# usb_ethernet.net
KiCad netlist of a schematic drawn in Altium Designer
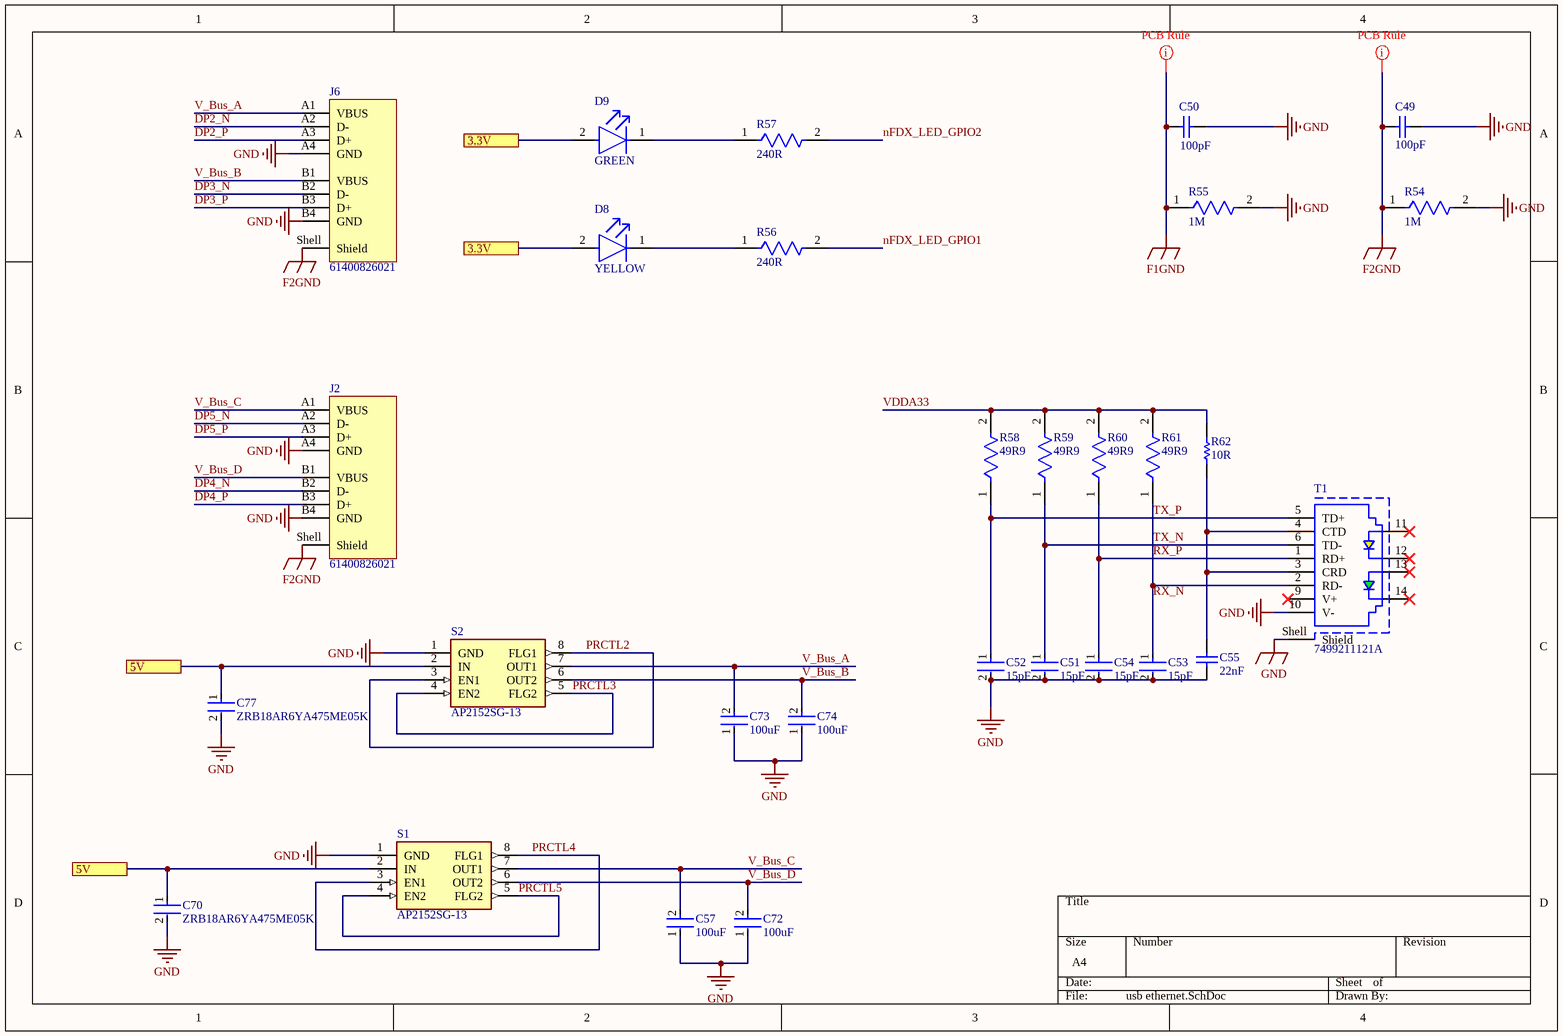
[diagram p0: usb ethernet.SchDoc]

(export (version "E")
  (design (tool "Eeschema 10.0.6"))
  (components
    (comp (ref "C49")
      (value "100pF")
      (footprint "CAPC1608X95X40LL15T15")
      (fields (field (name "PART NUMBER") "VJ0603Y101KXQPW1BC") (field (name "MANUFACTURER") "Vitramon"))
      (libsource (lib "Altium Content Vault") (part "CAP"))
    )
    (comp (ref "C50")
      (value "100pF")
      (footprint "CAPC1608X95X40LL15T15")
      (fields (field (name "PART NUMBER") "VJ0603Y101KXQPW1BC") (field (name "MANUFACTURER") "Vitramon"))
      (libsource (lib "Altium Content Vault") (part "CAP"))
    )
    (comp (ref "C51")
      (value "15pF")
      (footprint "FP-GRM21A-0_2-IPC_C")
      (description "Chip Multilayer Ceramic Capacitors for General Purpose, 0805, 15pF, C0G, 30ppm/°C, 1%, 250V")
      (libsource (lib "Altium Content Vault") (part "02cd4be3c70576c341d710602a673aa"))
    )
    (comp (ref "C52")
      (value "15pF")
      (footprint "FP-GRM21A-0_2-IPC_C")
      (description "Chip Multilayer Ceramic Capacitors for General Purpose, 0805, 15pF, C0G, 30ppm/°C, 1%, 250V")
      (libsource (lib "Altium Content Vault") (part "02cd4be3c70576c341d710602a673aa"))
    )
    (comp (ref "C53")
      (value "15pF")
      (footprint "FP-GRM21A-0_2-IPC_C")
      (description "Chip Multilayer Ceramic Capacitors for General Purpose, 0805, 15pF, C0G, 30ppm/°C, 1%, 250V")
      (libsource (lib "Altium Content Vault") (part "02cd4be3c70576c341d710602a673aa"))
    )
    (comp (ref "C54")
      (value "15pF")
      (footprint "FP-GRM21A-0_2-IPC_C")
      (description "Chip Multilayer Ceramic Capacitors for General Purpose, 0805, 15pF, C0G, 30ppm/°C, 1%, 250V")
      (libsource (lib "Altium Content Vault") (part "02cd4be3c70576c341d710602a673aa"))
    )
    (comp (ref "C55")
      (value "22nF")
      (footprint "CAPC2013X94X50ML20T25")
      (fields
        (field (name "PART NUMBER") "08055C223KAZ2A")
        (field (name "MANUFACTURER") "AVX Interconnect / Elco")
      )
      (libsource (lib "Altium Content Vault") (part "CAP"))
    )
    (comp (ref "C57")
      (value "100uF")
      (footprint "FP-GRM31C-0_3-e0_3_0_8-MFG")
      (description "Chip Multilayer Ceramic Capacitors for General Purpose, 1206, 100uF, X5R, 15%, 20%, 6.3V")
      (libsource (lib "Altium Content Vault") (part "f23184f103b6ebe33a8c269c53dcba6"))
    )
    (comp (ref "C70")
      (value "ZRB18AR6YA475ME05K")
      (footprint "FP-ZRB18A-0_2-MFG")
      (description "Chip Multilayer Ceramic Capacitors 4.7μF ±20% 35Vdc X5R ±15.0% 0603 (1608M)")
      (libsource (lib "Altium Content Vault") (part "b4654b650e69147ec39a6b967a45e02"))
    )
    (comp (ref "C72")
      (value "100uF")
      (footprint "FP-GRM31C-0_3-e0_3_0_8-MFG")
      (description "Chip Multilayer Ceramic Capacitors for General Purpose, 1206, 100uF, X5R, 15%, 20%, 6.3V")
      (libsource (lib "Altium Content Vault") (part "f23184f103b6ebe33a8c269c53dcba6"))
    )
    (comp (ref "C73")
      (value "100uF")
      (footprint "FP-GRM31C-0_3-e0_3_0_8-MFG")
      (description "Chip Multilayer Ceramic Capacitors for General Purpose, 1206, 100uF, X5R, 15%, 20%, 6.3V")
      (libsource (lib "Altium Content Vault") (part "f23184f103b6ebe33a8c269c53dcba6"))
    )
    (comp (ref "C74")
      (value "100uF")
      (footprint "FP-GRM31C-0_3-e0_3_0_8-MFG")
      (description "Chip Multilayer Ceramic Capacitors for General Purpose, 1206, 100uF, X5R, 15%, 20%, 6.3V")
      (libsource (lib "Altium Content Vault") (part "f23184f103b6ebe33a8c269c53dcba6"))
    )
    (comp (ref "C77")
      (value "ZRB18AR6YA475ME05K")
      (footprint "FP-ZRB18A-0_2-MFG")
      (description "Chip Multilayer Ceramic Capacitors 4.7μF ±20% 35Vdc X5R ±15.0% 0603 (1608M)")
      (libsource (lib "Altium Content Vault") (part "b4654b650e69147ec39a6b967a45e02"))
    )
    (comp (ref "D8")
      (value "YELLOW")
      (footprint "FP-APHCM2012SYCK-F01-MFG")
      (description "LED YELLOW CLEAR CHIP SMD")
      (libsource (lib "Altium Content Vault") (part "8706943c75ba83719d021d2fdc84c58"))
    )
    (comp (ref "D9")
      (value "GREEN")
      (footprint "FP-XZVG53W-1-MFG")
      (description "LED GREEN CLEAR CHIP SMD")
      (libsource (lib "Altium Content Vault") (part "8706943c75ba83719d021d2fdc84c58"))
    )
    (comp (ref "J2")
      (value "61400826021")
      (footprint "61400826021")
      (libsource (lib "Altium Content Vault") (part "USB 2.0_Type A_Receptacle_2 Port"))
    )
    (comp (ref "J6")
      (value "61400826021")
      (footprint "61400826021")
      (libsource (lib "Altium Content Vault") (part "USB 2.0_Type A_Receptacle_2 Port"))
    )
    (comp (ref "R54")
      (value "1M")
      (footprint "FP-RMCF0805-MFG")
      (description "1MΩ ±5% 0.125W 0805 Thick Film Chip Resistor AEC-Q200 compliant")
      (fields (field (name "TOLERANCE") "5%"))
      (libsource (lib "Altium Content Vault") (part "1029c3af85768c4190bb7ad29bc67b5"))
    )
    (comp (ref "R55")
      (value "1M")
      (footprint "FP-RMCF0805-MFG")
      (description "1MΩ ±5% 0.125W 0805 Thick Film Chip Resistor AEC-Q200 compliant")
      (fields (field (name "TOLERANCE") "5%"))
      (libsource (lib "Altium Content Vault") (part "1029c3af85768c4190bb7ad29bc67b5"))
    )
    (comp (ref "R56")
      (value "240R")
      (footprint "FP-RMCF0201-IPC_C")
      (description "240Ω ±1% 0.05W 0201 Thick Film Chip Resistor AEC-Q200 compliant")
      (fields (field (name "TOLERANCE") "1%"))
      (libsource (lib "Altium Content Vault") (part "1029c3af85768c4190bb7ad29bc67b5"))
    )
    (comp (ref "R57")
      (value "240R")
      (footprint "FP-RMCF0201-IPC_C")
      (description "240Ω ±1% 0.05W 0201 Thick Film Chip Resistor AEC-Q200 compliant")
      (fields (field (name "TOLERANCE") "1%"))
      (libsource (lib "Altium Content Vault") (part "1029c3af85768c4190bb7ad29bc67b5"))
    )
    (comp (ref "R58")
      (value "49R9")
      (footprint "FP-CPF0603-MFG")
      (description "RES SMD 49.9Ω 0.1% 1/16W 0603")
      (fields (field (name "TOLERANCE") "0.1%") (field (name "MANUFACTURER") "TE Connectivity"))
      (libsource (lib "Altium Content Vault") (part "1029c3af85768c4190bb7ad29bc67b5"))
    )
    (comp (ref "R59")
      (value "49R9")
      (footprint "FP-CPF0603-MFG")
      (description "RES SMD 49.9Ω 0.1% 1/16W 0603")
      (fields (field (name "TOLERANCE") "0.1%") (field (name "MANUFACTURER") "TE Connectivity"))
      (libsource (lib "Altium Content Vault") (part "1029c3af85768c4190bb7ad29bc67b5"))
    )
    (comp (ref "R60")
      (value "49R9")
      (footprint "FP-CPF0603-MFG")
      (description "RES SMD 49.9Ω 0.1% 1/16W 0603")
      (fields (field (name "TOLERANCE") "0.1%") (field (name "MANUFACTURER") "TE Connectivity"))
      (libsource (lib "Altium Content Vault") (part "1029c3af85768c4190bb7ad29bc67b5"))
    )
    (comp (ref "R61")
      (value "49R9")
      (footprint "FP-CPF0603-MFG")
      (description "RES SMD 49.9Ω 0.1% 1/16W 0603")
      (fields (field (name "TOLERANCE") "0.1%") (field (name "MANUFACTURER") "TE Connectivity"))
      (libsource (lib "Altium Content Vault") (part "1029c3af85768c4190bb7ad29bc67b5"))
    )
    (comp (ref "R62")
      (value "10R")
      (footprint "RESC1005X40X25LL10T10")
      (fields (field (name "PART NUMBER") "SG73P1ETTP10R0F") (field (name "MANUFACTURER") "KOA Speer"))
      (libsource (lib "Altium Content Vault") (part "RES"))
    )
    (comp (ref "S1")
      (value "AP2152SG-13")
      (footprint "SamacSys:SOIC127P600X175-8N")
      (description "Switch")
      (fields (field (name "MOUSER PART NUMBER") "621-AP2152SG-13"))
      (libsource (lib "*") (part "AP2152SG-13"))
    )
    (comp (ref "S2")
      (value "AP2152SG-13")
      (footprint "SamacSys:SOIC127P600X175-8N")
      (description "Switch")
      (fields (field (name "MOUSER PART NUMBER") "621-AP2152SG-13"))
      (libsource (lib "*") (part "AP2152SG-13"))
    )
    (comp (ref "T1")
      (value "7499211121A")
      (footprint "7499211121A")
      (description "7499211121A Modular Connectors / Ethernet Connectors WE-RJ45 Int XFMR THT 1x1")
      (libsource (lib "Altium Content Vault") (part "7499211121A"))
    )
  )
  (nets
    (net (code "1") (name "/3.3V") (class "Default")
      (node (ref "D8") (pin "2") (pinfunction "A_2") (pintype "passive"))
      (node (ref "D9") (pin "2") (pinfunction "A_2") (pintype "passive"))
    )
    (net (code "2") (name "/5V") (class "Default")
      (node (ref "C70") (pin "1") (pinfunction "1_1") (pintype "passive"))
      (node (ref "C77") (pin "1") (pinfunction "1_1") (pintype "passive"))
      (node (ref "S1") (pin "2") (pinfunction "IN_2") (pintype "power_in"))
      (node (ref "S2") (pin "2") (pinfunction "IN_2") (pintype "power_in"))
    )
    (net (code "3") (name "/DP2_N") (class "Default")
      (node (ref "J6") (pin "A2") (pinfunction "D-_A2") (pintype "passive"))
    )
    (net (code "4") (name "/DP2_P") (class "Default")
      (node (ref "J6") (pin "A3") (pinfunction "D+_A3") (pintype "passive"))
    )
    (net (code "5") (name "/DP3_N") (class "Default")
      (node (ref "J6") (pin "B2") (pinfunction "D-_B2") (pintype "passive"))
    )
    (net (code "6") (name "/DP3_P") (class "Default")
      (node (ref "J6") (pin "B3") (pinfunction "D+_B3") (pintype "passive"))
    )
    (net (code "7") (name "/DP4_N") (class "Default")
      (node (ref "J2") (pin "B2") (pinfunction "D-_B2") (pintype "passive"))
    )
    (net (code "8") (name "/DP4_P") (class "Default")
      (node (ref "J2") (pin "B3") (pinfunction "D+_B3") (pintype "passive"))
    )
    (net (code "9") (name "/DP5_N") (class "Default")
      (node (ref "J2") (pin "A2") (pinfunction "D-_A2") (pintype "passive"))
    )
    (net (code "10") (name "/DP5_P") (class "Default")
      (node (ref "J2") (pin "A3") (pinfunction "D+_A3") (pintype "passive"))
    )
    (net (code "11") (name "/PRCTL2") (class "Default")
      (node (ref "S2") (pin "3") (pinfunction "EN1_3") (pintype "input"))
      (node (ref "S2") (pin "8") (pinfunction "FLG1_8") (pintype "output"))
    )
    (net (code "12") (name "/PRCTL3") (class "Default")
      (node (ref "S2") (pin "4") (pinfunction "EN2_4") (pintype "input"))
      (node (ref "S2") (pin "5") (pinfunction "FLG2_5") (pintype "output"))
    )
    (net (code "13") (name "/PRCTL4") (class "Default")
      (node (ref "S1") (pin "3") (pinfunction "EN1_3") (pintype "input"))
      (node (ref "S1") (pin "8") (pinfunction "FLG1_8") (pintype "output"))
    )
    (net (code "14") (name "/PRCTL5") (class "Default")
      (node (ref "S1") (pin "4") (pinfunction "EN2_4") (pintype "input"))
      (node (ref "S1") (pin "5") (pinfunction "FLG2_5") (pintype "output"))
    )
    (net (code "15") (name "/RX_N") (class "Default")
      (node (ref "C51") (pin "1") (pinfunction "1_1") (pintype "passive"))
      (node (ref "C52") (pin "1") (pinfunction "1_1") (pintype "passive"))
      (node (ref "C53") (pin "1") (pinfunction "1_1") (pintype "passive"))
      (node (ref "C54") (pin "1") (pinfunction "1_1") (pintype "passive"))
      (node (ref "R58") (pin "1") (pinfunction "1_1") (pintype "passive"))
      (node (ref "R59") (pin "1") (pinfunction "1_1") (pintype "passive"))
      (node (ref "R60") (pin "1") (pinfunction "1_1") (pintype "passive"))
      (node (ref "R61") (pin "1") (pinfunction "1_1") (pintype "passive"))
      (node (ref "T1") (pin "1") (pinfunction "RD+_1") (pintype "passive"))
      (node (ref "T1") (pin "2") (pinfunction "RD-_2") (pintype "passive"))
      (node (ref "T1") (pin "5") (pinfunction "TD+_5") (pintype "passive"))
      (node (ref "T1") (pin "6") (pinfunction "TD-_6") (pintype "passive"))
    )
    (net (code "16") (name "/VDDA33") (class "Default")
      (node (ref "R58") (pin "2") (pinfunction "2_2") (pintype "passive"))
      (node (ref "R59") (pin "2") (pinfunction "2_2") (pintype "passive"))
      (node (ref "R60") (pin "2") (pinfunction "2_2") (pintype "passive"))
      (node (ref "R61") (pin "2") (pinfunction "2_2") (pintype "passive"))
      (node (ref "R62") (pin "2") (pinfunction "2_2") (pintype "passive"))
    )
    (net (code "17") (name "/V_Bus_A") (class "Default")
      (node (ref "C73") (pin "2") (pinfunction "2_2") (pintype "passive"))
      (node (ref "J6") (pin "A1") (pinfunction "VBUS_A1") (pintype "passive"))
      (node (ref "S2") (pin "7") (pinfunction "OUT1_7") (pintype "output"))
    )
    (net (code "18") (name "/V_Bus_B") (class "Default")
      (node (ref "C74") (pin "2") (pinfunction "2_2") (pintype "passive"))
      (node (ref "J6") (pin "B1") (pinfunction "VBUS_B1") (pintype "passive"))
      (node (ref "S2") (pin "6") (pinfunction "OUT2_6") (pintype "output"))
    )
    (net (code "19") (name "/V_Bus_C") (class "Default")
      (node (ref "C57") (pin "2") (pinfunction "2_2") (pintype "passive"))
      (node (ref "J2") (pin "A1") (pinfunction "VBUS_A1") (pintype "passive"))
      (node (ref "S1") (pin "7") (pinfunction "OUT1_7") (pintype "output"))
    )
    (net (code "20") (name "/V_Bus_D") (class "Default")
      (node (ref "C72") (pin "2") (pinfunction "2_2") (pintype "passive"))
      (node (ref "J2") (pin "B1") (pinfunction "VBUS_B1") (pintype "passive"))
      (node (ref "S1") (pin "6") (pinfunction "OUT2_6") (pintype "output"))
    )
    (net (code "21") (name "/nFDX_LED_GPIO1") (class "Default")
      (node (ref "R56") (pin "2") (pinfunction "2_2") (pintype "passive"))
    )
    (net (code "22") (name "/nFDX_LED_GPIO2") (class "Default")
      (node (ref "R57") (pin "2") (pinfunction "2_2") (pintype "passive"))
    )
    (net (code "23") (name "F1GND") (class "Default")
      (node (ref "C50") (pin "1") (pinfunction "1_1") (pintype "passive"))
      (node (ref "R55") (pin "1") (pinfunction "1_1") (pintype "passive"))
    )
    (net (code "24") (name "F2GND") (class "Default")
      (node (ref "C49") (pin "1") (pinfunction "1_1") (pintype "passive"))
      (node (ref "J2") (pin "Shell") (pinfunction "Shield_Shell") (pintype "passive"))
      (node (ref "J6") (pin "Shell") (pinfunction "Shield_Shell") (pintype "passive"))
      (node (ref "R54") (pin "1") (pinfunction "1_1") (pintype "passive"))
    )
    (net (code "25") (name "GND") (class "Default")
      (node (ref "C49") (pin "2") (pinfunction "2_2") (pintype "passive"))
      (node (ref "C50") (pin "2") (pinfunction "2_2") (pintype "passive"))
      (node (ref "C51") (pin "2") (pinfunction "2_2") (pintype "passive"))
      (node (ref "C52") (pin "2") (pinfunction "2_2") (pintype "passive"))
      (node (ref "C53") (pin "2") (pinfunction "2_2") (pintype "passive"))
      (node (ref "C54") (pin "2") (pinfunction "2_2") (pintype "passive"))
      (node (ref "C55") (pin "1") (pinfunction "1_1") (pintype "passive"))
      (node (ref "C57") (pin "1") (pinfunction "1_1") (pintype "passive"))
      (node (ref "C70") (pin "2") (pinfunction "2_2") (pintype "passive"))
      (node (ref "C72") (pin "1") (pinfunction "1_1") (pintype "passive"))
      (node (ref "C73") (pin "1") (pinfunction "1_1") (pintype "passive"))
      (node (ref "C74") (pin "1") (pinfunction "1_1") (pintype "passive"))
      (node (ref "C77") (pin "2") (pinfunction "2_2") (pintype "passive"))
      (node (ref "J2") (pin "A4") (pinfunction "GND_A4") (pintype "passive"))
      (node (ref "J2") (pin "B4") (pinfunction "GND_B4") (pintype "passive"))
      (node (ref "J6") (pin "A4") (pinfunction "GND_A4") (pintype "passive"))
      (node (ref "J6") (pin "B4") (pinfunction "GND_B4") (pintype "passive"))
      (node (ref "R54") (pin "2") (pinfunction "2_2") (pintype "passive"))
      (node (ref "R55") (pin "2") (pinfunction "2_2") (pintype "passive"))
      (node (ref "S1") (pin "1") (pinfunction "GND_1") (pintype "power_in"))
      (node (ref "S2") (pin "1") (pinfunction "GND_1") (pintype "power_in"))
      (node (ref "T1") (pin "10") (pinfunction "V-_10") (pintype "passive"))
      (node (ref "T1") (pin "Shell") (pinfunction "Shield_Shell") (pintype "passive"))
    )
    (net (code "26") (name "Net-(D8-C)") (class "Default")
      (node (ref "D8") (pin "1") (pinfunction "C_1") (pintype "passive"))
      (node (ref "R56") (pin "1") (pinfunction "1_1") (pintype "passive"))
    )
    (net (code "27") (name "Net-(D9-C)") (class "Default")
      (node (ref "D9") (pin "1") (pinfunction "C_1") (pintype "passive"))
      (node (ref "R57") (pin "1") (pinfunction "1_1") (pintype "passive"))
    )
    (net (code "28") (name "Net-(T1-CRD)") (class "Default")
      (node (ref "C55") (pin "2") (pinfunction "2_2") (pintype "passive"))
      (node (ref "R62") (pin "1") (pinfunction "1_1") (pintype "passive"))
      (node (ref "T1") (pin "3") (pinfunction "CRD_3") (pintype "passive"))
      (node (ref "T1") (pin "4") (pinfunction "CTD_4") (pintype "passive"))
    )
    (net (code "29") (name "unconnected-(T1-Pad11)") (class "Default")
      (node (ref "T1") (pin "11") (pinfunction "11_11") (pintype "passive+no_connect"))
    )
    (net (code "30") (name "unconnected-(T1-Pad12)") (class "Default")
      (node (ref "T1") (pin "12") (pinfunction "12_12") (pintype "passive+no_connect"))
    )
    (net (code "31") (name "unconnected-(T1-Pad13)") (class "Default")
      (node (ref "T1") (pin "13") (pinfunction "13_13") (pintype "passive+no_connect"))
    )
    (net (code "32") (name "unconnected-(T1-Pad14)") (class "Default")
      (node (ref "T1") (pin "14") (pinfunction "14_14") (pintype "passive+no_connect"))
    )
    (net (code "33") (name "unconnected-(T1-V+-Pad9)") (class "Default")
      (node (ref "T1") (pin "9") (pinfunction "V+_9") (pintype "passive+no_connect"))
    )
  )
)
